# Hardware-Neuron.net
KiCad netlist of a schematic drawn in EAGLE
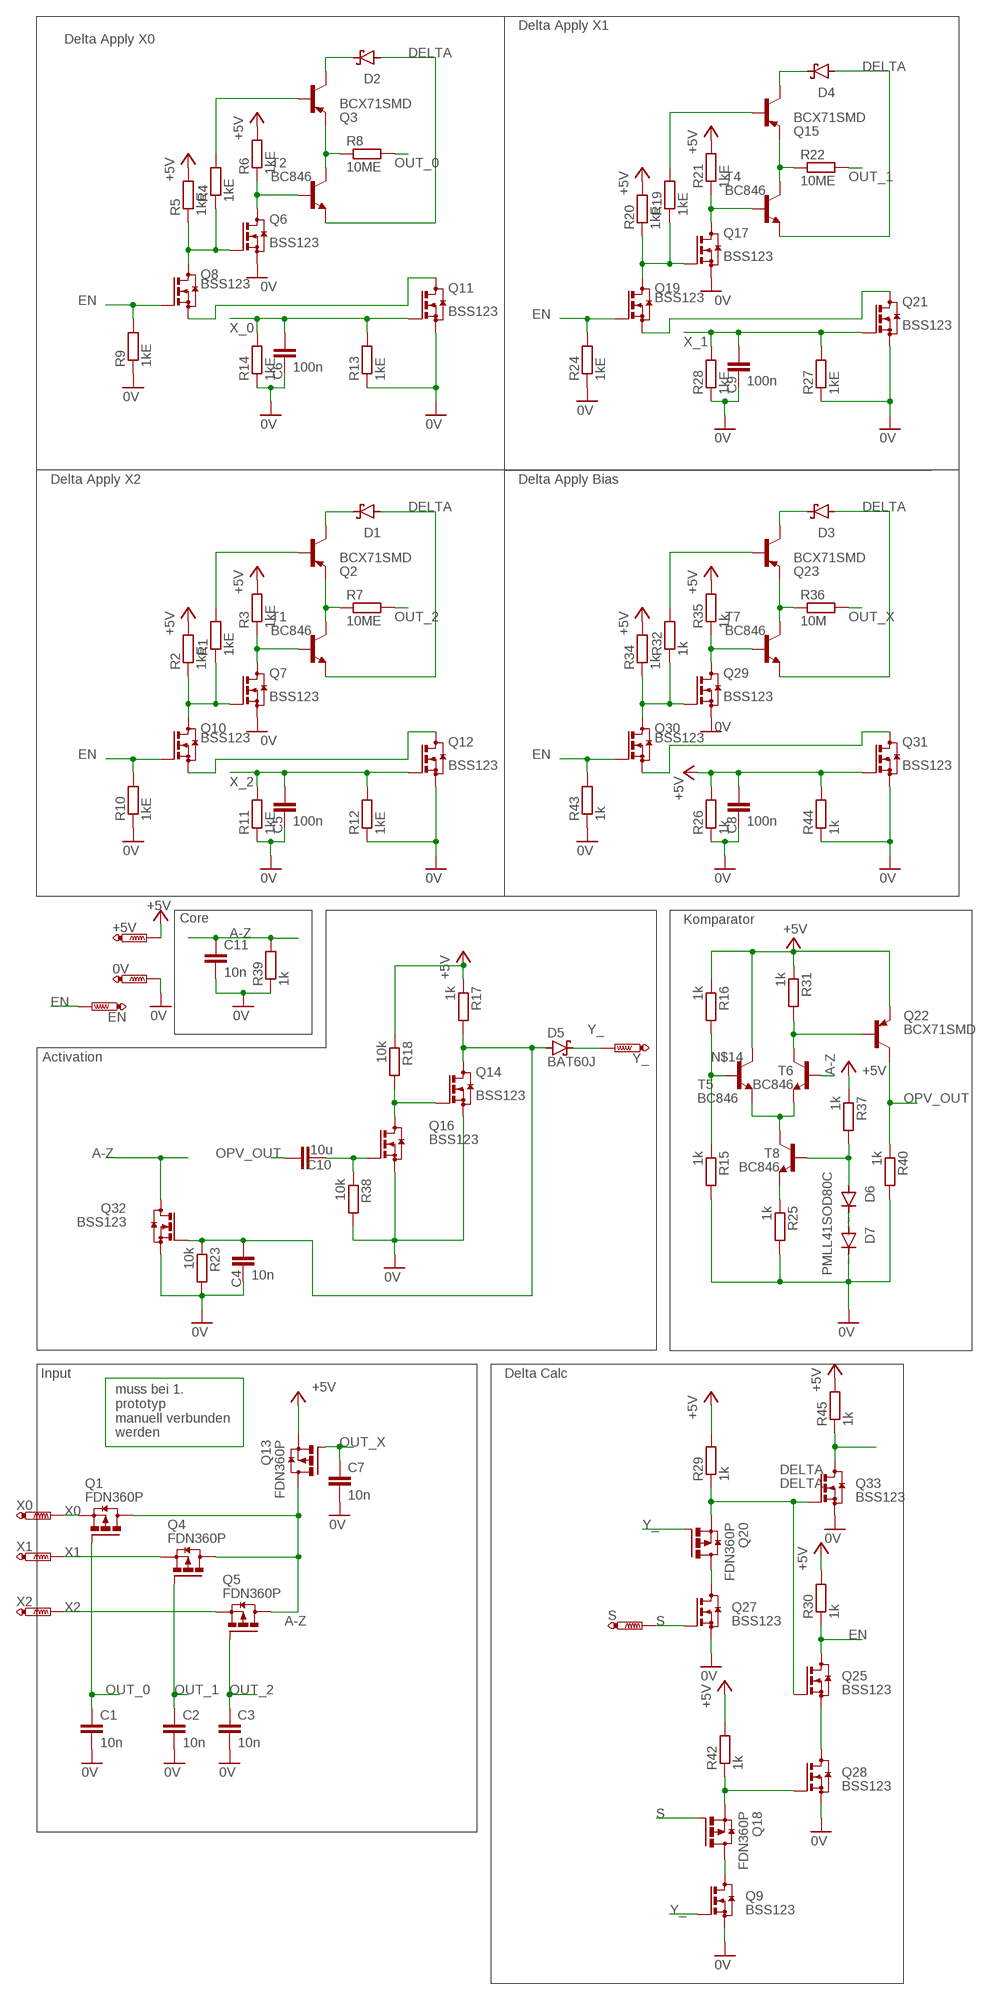
[diagram p0: schematic, sheet 1]

(export (version "E")
  (design (tool "Eeschema 10.0.6"))
  (components
    (comp (ref "+5V")
      (value "PTR1PAD1-17")
      (footprint "eagle-import:P1-17")
      (libsource (lib "eagle-import") (part "PTR1PAD1-17"))
    )
    (comp (ref "0V")
      (value "PTR1PAD1-17")
      (footprint "eagle-import:P1-17")
      (libsource (lib "eagle-import") (part "PTR1PAD1-17"))
    )
    (comp (ref "C1")
      (value "10n")
      (footprint "eagle-import:C0805")
      (libsource (lib "eagle-import") (part "C-EUC0805"))
    )
    (comp (ref "C2")
      (value "10n")
      (footprint "eagle-import:C0805")
      (libsource (lib "eagle-import") (part "C-EUC0805"))
    )
    (comp (ref "C3")
      (value "10n")
      (footprint "eagle-import:C0805")
      (libsource (lib "eagle-import") (part "C-EUC0805"))
    )
    (comp (ref "C4")
      (value "10n")
      (footprint "eagle-import:C0805")
      (libsource (lib "eagle-import") (part "C-EUC0805"))
    )
    (comp (ref "C5")
      (value "100n")
      (footprint "eagle-import:C0805")
      (libsource (lib "eagle-import") (part "C-EUC0805"))
    )
    (comp (ref "C6")
      (value "100n")
      (footprint "eagle-import:C0805")
      (libsource (lib "eagle-import") (part "C-EUC0805"))
    )
    (comp (ref "C7")
      (value "10n")
      (footprint "eagle-import:C0805")
      (libsource (lib "eagle-import") (part "C-EUC0805"))
    )
    (comp (ref "C8")
      (value "100n")
      (footprint "eagle-import:C0805")
      (libsource (lib "eagle-import") (part "C-EUC0805"))
    )
    (comp (ref "C9")
      (value "100n")
      (footprint "eagle-import:C0805")
      (libsource (lib "eagle-import") (part "C-EUC0805"))
    )
    (comp (ref "C10")
      (value "10u")
      (footprint "eagle-import:C0805")
      (libsource (lib "eagle-import") (part "C-EUC0805"))
    )
    (comp (ref "C11")
      (value "10n")
      (footprint "eagle-import:C0805")
      (libsource (lib "eagle-import") (part "C-EUC0805"))
    )
    (comp (ref "D1")
      (value "BAT60J")
      (footprint "eagle-import:SOD323_ST")
      (libsource (lib "eagle-import") (part "BAT60J"))
    )
    (comp (ref "D2")
      (value "BAT60J")
      (footprint "eagle-import:SOD323_ST")
      (libsource (lib "eagle-import") (part "BAT60J"))
    )
    (comp (ref "D3")
      (value "BAT60J")
      (footprint "eagle-import:SOD323_ST")
      (libsource (lib "eagle-import") (part "BAT60J"))
    )
    (comp (ref "D4")
      (value "BAT60J")
      (footprint "eagle-import:SOD323_ST")
      (libsource (lib "eagle-import") (part "BAT60J"))
    )
    (comp (ref "D5")
      (value "BAT60J")
      (footprint "eagle-import:SOD323_ST")
      (libsource (lib "eagle-import") (part "BAT60J"))
    )
    (comp (ref "D6")
      (value "PMLL41SOD80C")
      (footprint "eagle-import:SOD80C")
      (libsource (lib "eagle-import") (part "PMLL41SOD80C"))
    )
    (comp (ref "D7")
      (value "PMLL41SOD80C")
      (footprint "eagle-import:SOD80C")
      (libsource (lib "eagle-import") (part "PMLL41SOD80C"))
    )
    (comp (ref "EN")
      (value "PTR1PAD1-17")
      (footprint "eagle-import:P1-17")
      (libsource (lib "eagle-import") (part "PTR1PAD1-17"))
    )
    (comp (ref "Q1")
      (value "FDN360P")
      (footprint "eagle-import:SUPER-SOT3")
      (libsource (lib "eagle-import") (part "FDN360P"))
    )
    (comp (ref "Q2")
      (value "BCX71SMD")
      (footprint "eagle-import:SOT23")
      (libsource (lib "eagle-import") (part "BCX71SMD"))
    )
    (comp (ref "Q3")
      (value "BCX71SMD")
      (footprint "eagle-import:SOT23")
      (libsource (lib "eagle-import") (part "BCX71SMD"))
    )
    (comp (ref "Q4")
      (value "FDN360P")
      (footprint "eagle-import:SUPER-SOT3")
      (libsource (lib "eagle-import") (part "FDN360P"))
    )
    (comp (ref "Q5")
      (value "FDN360P")
      (footprint "eagle-import:SUPER-SOT3")
      (libsource (lib "eagle-import") (part "FDN360P"))
    )
    (comp (ref "Q6")
      (value "BSS123")
      (footprint "eagle-import:SOT23")
      (libsource (lib "eagle-import") (part "BSS123"))
    )
    (comp (ref "Q7")
      (value "BSS123")
      (footprint "eagle-import:SOT23")
      (libsource (lib "eagle-import") (part "BSS123"))
    )
    (comp (ref "Q8")
      (value "BSS123")
      (footprint "eagle-import:SOT23")
      (libsource (lib "eagle-import") (part "BSS123"))
    )
    (comp (ref "Q9")
      (value "BSS123")
      (footprint "eagle-import:SOT23")
      (libsource (lib "eagle-import") (part "BSS123"))
    )
    (comp (ref "Q10")
      (value "BSS123")
      (footprint "eagle-import:SOT23")
      (libsource (lib "eagle-import") (part "BSS123"))
    )
    (comp (ref "Q11")
      (value "BSS123")
      (footprint "eagle-import:SOT23")
      (libsource (lib "eagle-import") (part "BSS123"))
    )
    (comp (ref "Q12")
      (value "BSS123")
      (footprint "eagle-import:SOT23")
      (libsource (lib "eagle-import") (part "BSS123"))
    )
    (comp (ref "Q13")
      (value "FDN360P")
      (footprint "eagle-import:SUPER-SOT3")
      (libsource (lib "eagle-import") (part "FDN360P"))
    )
    (comp (ref "Q14")
      (value "BSS123")
      (footprint "eagle-import:SOT23")
      (libsource (lib "eagle-import") (part "BSS123"))
    )
    (comp (ref "Q15")
      (value "BCX71SMD")
      (footprint "eagle-import:SOT23")
      (libsource (lib "eagle-import") (part "BCX71SMD"))
    )
    (comp (ref "Q16")
      (value "BSS123")
      (footprint "eagle-import:SOT23")
      (libsource (lib "eagle-import") (part "BSS123"))
    )
    (comp (ref "Q17")
      (value "BSS123")
      (footprint "eagle-import:SOT23")
      (libsource (lib "eagle-import") (part "BSS123"))
    )
    (comp (ref "Q18")
      (value "FDN360P")
      (footprint "eagle-import:SUPER-SOT3")
      (libsource (lib "eagle-import") (part "FDN360P"))
    )
    (comp (ref "Q19")
      (value "BSS123")
      (footprint "eagle-import:SOT23")
      (libsource (lib "eagle-import") (part "BSS123"))
    )
    (comp (ref "Q20")
      (value "FDN360P")
      (footprint "eagle-import:SUPER-SOT3")
      (libsource (lib "eagle-import") (part "FDN360P"))
    )
    (comp (ref "Q21")
      (value "BSS123")
      (footprint "eagle-import:SOT23")
      (libsource (lib "eagle-import") (part "BSS123"))
    )
    (comp (ref "Q22")
      (value "BCX71SMD")
      (footprint "eagle-import:SOT23")
      (libsource (lib "eagle-import") (part "BCX71SMD"))
    )
    (comp (ref "Q23")
      (value "BCX71SMD")
      (footprint "eagle-import:SOT23")
      (libsource (lib "eagle-import") (part "BCX71SMD"))
    )
    (comp (ref "Q25")
      (value "BSS123")
      (footprint "eagle-import:SOT23")
      (libsource (lib "eagle-import") (part "BSS123"))
    )
    (comp (ref "Q27")
      (value "BSS123")
      (footprint "eagle-import:SOT23")
      (libsource (lib "eagle-import") (part "BSS123"))
    )
    (comp (ref "Q28")
      (value "BSS123")
      (footprint "eagle-import:SOT23")
      (libsource (lib "eagle-import") (part "BSS123"))
    )
    (comp (ref "Q29")
      (value "BSS123")
      (footprint "eagle-import:SOT23")
      (libsource (lib "eagle-import") (part "BSS123"))
    )
    (comp (ref "Q30")
      (value "BSS123")
      (footprint "eagle-import:SOT23")
      (libsource (lib "eagle-import") (part "BSS123"))
    )
    (comp (ref "Q31")
      (value "BSS123")
      (footprint "eagle-import:SOT23")
      (libsource (lib "eagle-import") (part "BSS123"))
    )
    (comp (ref "Q32")
      (value "BSS123")
      (footprint "eagle-import:SOT23")
      (libsource (lib "eagle-import") (part "BSS123"))
    )
    (comp (ref "Q33")
      (value "BSS123")
      (footprint "eagle-import:SOT23")
      (libsource (lib "eagle-import") (part "BSS123"))
    )
    (comp (ref "R1")
      (value "1kE")
      (footprint "eagle-import:M0805")
      (libsource (lib "eagle-import") (part "R-EU_M0805"))
    )
    (comp (ref "R2")
      (value "1kE")
      (footprint "eagle-import:M0805")
      (libsource (lib "eagle-import") (part "R-EU_M0805"))
    )
    (comp (ref "R3")
      (value "1kE")
      (footprint "eagle-import:M0805")
      (libsource (lib "eagle-import") (part "R-EU_M0805"))
    )
    (comp (ref "R4")
      (value "1kE")
      (footprint "eagle-import:M0805")
      (libsource (lib "eagle-import") (part "R-EU_M0805"))
    )
    (comp (ref "R5")
      (value "1kE")
      (footprint "eagle-import:M0805")
      (libsource (lib "eagle-import") (part "R-EU_M0805"))
    )
    (comp (ref "R6")
      (value "1kE")
      (footprint "eagle-import:M0805")
      (libsource (lib "eagle-import") (part "R-EU_M0805"))
    )
    (comp (ref "R7")
      (value "10ME")
      (footprint "eagle-import:M0805")
      (libsource (lib "eagle-import") (part "R-EU_M0805"))
    )
    (comp (ref "R8")
      (value "10ME")
      (footprint "eagle-import:M0805")
      (libsource (lib "eagle-import") (part "R-EU_M0805"))
    )
    (comp (ref "R9")
      (value "1kE")
      (footprint "eagle-import:M0805")
      (libsource (lib "eagle-import") (part "R-EU_M0805"))
    )
    (comp (ref "R10")
      (value "1kE")
      (footprint "eagle-import:M0805")
      (libsource (lib "eagle-import") (part "R-EU_M0805"))
    )
    (comp (ref "R11")
      (value "1kE")
      (footprint "eagle-import:M0805")
      (libsource (lib "eagle-import") (part "R-EU_M0805"))
    )
    (comp (ref "R12")
      (value "1kE")
      (footprint "eagle-import:M0805")
      (libsource (lib "eagle-import") (part "R-EU_M0805"))
    )
    (comp (ref "R13")
      (value "1kE")
      (footprint "eagle-import:M0805")
      (libsource (lib "eagle-import") (part "R-EU_M0805"))
    )
    (comp (ref "R14")
      (value "1kE")
      (footprint "eagle-import:M0805")
      (libsource (lib "eagle-import") (part "R-EU_M0805"))
    )
    (comp (ref "R15")
      (value "1k")
      (footprint "eagle-import:M0805")
      (libsource (lib "eagle-import") (part "R-EU_M0805"))
    )
    (comp (ref "R16")
      (value "1k")
      (footprint "eagle-import:M0805")
      (libsource (lib "eagle-import") (part "R-EU_M0805"))
    )
    (comp (ref "R17")
      (value "1k")
      (footprint "eagle-import:M0805")
      (libsource (lib "eagle-import") (part "R-EU_M0805"))
    )
    (comp (ref "R18")
      (value "10k")
      (footprint "eagle-import:M0805")
      (libsource (lib "eagle-import") (part "R-EU_M0805"))
    )
    (comp (ref "R19")
      (value "1kE")
      (footprint "eagle-import:M0805")
      (libsource (lib "eagle-import") (part "R-EU_M0805"))
    )
    (comp (ref "R20")
      (value "1kE")
      (footprint "eagle-import:M0805")
      (libsource (lib "eagle-import") (part "R-EU_M0805"))
    )
    (comp (ref "R21")
      (value "1kE")
      (footprint "eagle-import:M0805")
      (libsource (lib "eagle-import") (part "R-EU_M0805"))
    )
    (comp (ref "R22")
      (value "10ME")
      (footprint "eagle-import:M0805")
      (libsource (lib "eagle-import") (part "R-EU_M0805"))
    )
    (comp (ref "R23")
      (value "10k")
      (footprint "eagle-import:M0805")
      (libsource (lib "eagle-import") (part "R-EU_M0805"))
    )
    (comp (ref "R24")
      (value "1kE")
      (footprint "eagle-import:M0805")
      (libsource (lib "eagle-import") (part "R-EU_M0805"))
    )
    (comp (ref "R25")
      (value "1k")
      (footprint "eagle-import:M0805")
      (libsource (lib "eagle-import") (part "R-EU_M0805"))
    )
    (comp (ref "R26")
      (value "1k")
      (footprint "eagle-import:M0805")
      (libsource (lib "eagle-import") (part "R-EU_M0805"))
    )
    (comp (ref "R27")
      (value "1kE")
      (footprint "eagle-import:M0805")
      (libsource (lib "eagle-import") (part "R-EU_M0805"))
    )
    (comp (ref "R28")
      (value "1kE")
      (footprint "eagle-import:M0805")
      (libsource (lib "eagle-import") (part "R-EU_M0805"))
    )
    (comp (ref "R29")
      (value "1k")
      (footprint "eagle-import:M0805")
      (libsource (lib "eagle-import") (part "R-EU_M0805"))
    )
    (comp (ref "R30")
      (value "1k")
      (footprint "eagle-import:M0805")
      (libsource (lib "eagle-import") (part "R-EU_M0805"))
    )
    (comp (ref "R31")
      (value "1k")
      (footprint "eagle-import:M0805")
      (libsource (lib "eagle-import") (part "R-EU_M0805"))
    )
    (comp (ref "R32")
      (value "1k")
      (footprint "eagle-import:M0805")
      (libsource (lib "eagle-import") (part "R-EU_M0805"))
    )
    (comp (ref "R34")
      (value "1k")
      (footprint "eagle-import:M0805")
      (libsource (lib "eagle-import") (part "R-EU_M0805"))
    )
    (comp (ref "R35")
      (value "1k")
      (footprint "eagle-import:M0805")
      (libsource (lib "eagle-import") (part "R-EU_M0805"))
    )
    (comp (ref "R36")
      (value "10M")
      (footprint "eagle-import:M0805")
      (libsource (lib "eagle-import") (part "R-EU_M0805"))
    )
    (comp (ref "R37")
      (value "1k")
      (footprint "eagle-import:M0805")
      (libsource (lib "eagle-import") (part "R-EU_M0805"))
    )
    (comp (ref "R38")
      (value "10k")
      (footprint "eagle-import:M0805")
      (libsource (lib "eagle-import") (part "R-EU_M0805"))
    )
    (comp (ref "R39")
      (value "1k")
      (footprint "eagle-import:M0805")
      (libsource (lib "eagle-import") (part "R-EU_M0805"))
    )
    (comp (ref "R40")
      (value "1k")
      (footprint "eagle-import:M0805")
      (libsource (lib "eagle-import") (part "R-EU_M0805"))
    )
    (comp (ref "R42")
      (value "1k")
      (footprint "eagle-import:M0805")
      (libsource (lib "eagle-import") (part "R-EU_M0805"))
    )
    (comp (ref "R43")
      (value "1k")
      (footprint "eagle-import:M0805")
      (libsource (lib "eagle-import") (part "R-EU_M0805"))
    )
    (comp (ref "R44")
      (value "1k")
      (footprint "eagle-import:M0805")
      (libsource (lib "eagle-import") (part "R-EU_M0805"))
    )
    (comp (ref "R45")
      (value "1k")
      (footprint "eagle-import:M0805")
      (libsource (lib "eagle-import") (part "R-EU_M0805"))
    )
    (comp (ref "S")
      (value "PTR1PAD1-17")
      (footprint "eagle-import:P1-17")
      (libsource (lib "eagle-import") (part "PTR1PAD1-17"))
    )
    (comp (ref "T1")
      (value "BC846")
      (footprint "eagle-import:SOT23")
      (libsource (lib "eagle-import") (part "BC846"))
    )
    (comp (ref "T2")
      (value "BC846")
      (footprint "eagle-import:SOT23")
      (libsource (lib "eagle-import") (part "BC846"))
    )
    (comp (ref "T4")
      (value "BC846")
      (footprint "eagle-import:SOT23")
      (libsource (lib "eagle-import") (part "BC846"))
    )
    (comp (ref "T5")
      (value "BC846")
      (footprint "eagle-import:SOT23")
      (libsource (lib "eagle-import") (part "BC846"))
    )
    (comp (ref "T6")
      (value "BC846")
      (footprint "eagle-import:SOT23")
      (libsource (lib "eagle-import") (part "BC846"))
    )
    (comp (ref "T7")
      (value "BC846")
      (footprint "eagle-import:SOT23")
      (libsource (lib "eagle-import") (part "BC846"))
    )
    (comp (ref "T8")
      (value "BC846")
      (footprint "eagle-import:SOT23")
      (libsource (lib "eagle-import") (part "BC846"))
    )
    (comp (ref "X0")
      (value "PTR1PAD1-17")
      (footprint "eagle-import:P1-17")
      (libsource (lib "eagle-import") (part "PTR1PAD1-17"))
    )
    (comp (ref "X1")
      (value "PTR1PAD1-17")
      (footprint "eagle-import:P1-17")
      (libsource (lib "eagle-import") (part "PTR1PAD1-17"))
    )
    (comp (ref "X2")
      (value "PTR1PAD1-17")
      (footprint "eagle-import:P1-17")
      (libsource (lib "eagle-import") (part "PTR1PAD1-17"))
    )
    (comp (ref "Y_")
      (value "PTR1PAD1-17")
      (footprint "eagle-import:P1-17")
      (libsource (lib "eagle-import") (part "PTR1PAD1-17"))
    )
  )
  (nets
    (net (code "1") (name "+5V") (class "Default")
      (node (ref "+5V") (pin "TP") (pinfunction "TP_TP") (pintype "input"))
      (node (ref "C8") (pin "1") (pinfunction "1_1") (pintype "passive"))
      (node (ref "Q13") (pin "2") (pinfunction "S_2") (pintype "passive"))
      (node (ref "Q22") (pin "2") (pinfunction "E_2") (pintype "passive"))
      (node (ref "Q31") (pin "1") (pinfunction "G_1") (pintype "passive"))
      (node (ref "R16") (pin "1") (pinfunction "1_1") (pintype "passive"))
      (node (ref "R17") (pin "1") (pinfunction "1_1") (pintype "passive"))
      (node (ref "R18") (pin "1") (pinfunction "1_1") (pintype "passive"))
      (node (ref "R2") (pin "2") (pinfunction "2_2") (pintype "passive"))
      (node (ref "R20") (pin "2") (pinfunction "2_2") (pintype "passive"))
      (node (ref "R21") (pin "2") (pinfunction "2_2") (pintype "passive"))
      (node (ref "R26") (pin "2") (pinfunction "2_2") (pintype "passive"))
      (node (ref "R29") (pin "2") (pinfunction "2_2") (pintype "passive"))
      (node (ref "R3") (pin "2") (pinfunction "2_2") (pintype "passive"))
      (node (ref "R30") (pin "2") (pinfunction "2_2") (pintype "passive"))
      (node (ref "R31") (pin "1") (pinfunction "1_1") (pintype "passive"))
      (node (ref "R34") (pin "2") (pinfunction "2_2") (pintype "passive"))
      (node (ref "R35") (pin "2") (pinfunction "2_2") (pintype "passive"))
      (node (ref "R37") (pin "1") (pinfunction "1_1") (pintype "passive"))
      (node (ref "R42") (pin "2") (pinfunction "2_2") (pintype "passive"))
      (node (ref "R44") (pin "2") (pinfunction "2_2") (pintype "passive"))
      (node (ref "R45") (pin "2") (pinfunction "2_2") (pintype "passive"))
      (node (ref "R5") (pin "2") (pinfunction "2_2") (pintype "passive"))
      (node (ref "R6") (pin "2") (pinfunction "2_2") (pintype "passive"))
      (node (ref "T5") (pin "3") (pinfunction "C_3") (pintype "passive"))
    )
    (net (code "2") (name "/A-Z") (class "Default")
      (node (ref "C11") (pin "1") (pinfunction "1_1") (pintype "passive"))
      (node (ref "Q1") (pin "3") (pinfunction "D_3") (pintype "passive"))
      (node (ref "Q13") (pin "3") (pinfunction "D_3") (pintype "passive"))
      (node (ref "Q32") (pin "3") (pinfunction "D_3") (pintype "passive"))
      (node (ref "Q4") (pin "3") (pinfunction "D_3") (pintype "passive"))
      (node (ref "Q5") (pin "3") (pinfunction "D_3") (pintype "passive"))
      (node (ref "R39") (pin "2") (pinfunction "2_2") (pintype "passive"))
      (node (ref "T6") (pin "1") (pinfunction "B_1") (pintype "passive"))
    )
    (net (code "3") (name "/DELTA") (class "Default")
      (node (ref "D1") (pin "A") (pinfunction "A_A") (pintype "passive"))
      (node (ref "D2") (pin "A") (pinfunction "A_A") (pintype "passive"))
      (node (ref "D3") (pin "A") (pinfunction "A_A") (pintype "passive"))
      (node (ref "D4") (pin "A") (pinfunction "A_A") (pintype "passive"))
      (node (ref "Q20") (pin "2") (pinfunction "S_2") (pintype "passive"))
      (node (ref "Q25") (pin "1") (pinfunction "G_1") (pintype "passive"))
      (node (ref "Q33") (pin "1") (pinfunction "G_1") (pintype "passive"))
      (node (ref "R29") (pin "1") (pinfunction "1_1") (pintype "passive"))
      (node (ref "T1") (pin "2") (pinfunction "E_2") (pintype "passive"))
      (node (ref "T2") (pin "2") (pinfunction "E_2") (pintype "passive"))
      (node (ref "T4") (pin "2") (pinfunction "E_2") (pintype "passive"))
      (node (ref "T7") (pin "2") (pinfunction "E_2") (pintype "passive"))
    )
    (net (code "4") (name "/EN") (class "Default")
      (node (ref "EN") (pin "TP") (pinfunction "TP_TP") (pintype "input"))
      (node (ref "Q10") (pin "1") (pinfunction "G_1") (pintype "passive"))
      (node (ref "Q19") (pin "1") (pinfunction "G_1") (pintype "passive"))
      (node (ref "Q25") (pin "3") (pinfunction "D_3") (pintype "passive"))
      (node (ref "Q30") (pin "1") (pinfunction "G_1") (pintype "passive"))
      (node (ref "Q8") (pin "1") (pinfunction "G_1") (pintype "passive"))
      (node (ref "R10") (pin "2") (pinfunction "2_2") (pintype "passive"))
      (node (ref "R24") (pin "2") (pinfunction "2_2") (pintype "passive"))
      (node (ref "R30") (pin "1") (pinfunction "1_1") (pintype "passive"))
      (node (ref "R43") (pin "2") (pinfunction "2_2") (pintype "passive"))
      (node (ref "R9") (pin "2") (pinfunction "2_2") (pintype "passive"))
    )
    (net (code "5") (name "/N$14") (class "Default")
      (node (ref "R15") (pin "1") (pinfunction "1_1") (pintype "passive"))
      (node (ref "R16") (pin "2") (pinfunction "2_2") (pintype "passive"))
      (node (ref "T5") (pin "1") (pinfunction "B_1") (pintype "passive"))
    )
    (net (code "6") (name "/OPV_OUT") (class "Default")
      (node (ref "C10") (pin "1") (pinfunction "1_1") (pintype "passive"))
      (node (ref "Q22") (pin "3") (pinfunction "C_3") (pintype "passive"))
      (node (ref "R40") (pin "1") (pinfunction "1_1") (pintype "passive"))
    )
    (net (code "7") (name "/OUT_0") (class "Default")
      (node (ref "C1") (pin "1") (pinfunction "1_1") (pintype "passive"))
      (node (ref "Q1") (pin "1") (pinfunction "G_1") (pintype "passive"))
      (node (ref "R8") (pin "2") (pinfunction "2_2") (pintype "passive"))
    )
    (net (code "8") (name "/OUT_1") (class "Default")
      (node (ref "C2") (pin "1") (pinfunction "1_1") (pintype "passive"))
      (node (ref "Q4") (pin "1") (pinfunction "G_1") (pintype "passive"))
      (node (ref "R22") (pin "2") (pinfunction "2_2") (pintype "passive"))
    )
    (net (code "9") (name "/OUT_2") (class "Default")
      (node (ref "C3") (pin "1") (pinfunction "1_1") (pintype "passive"))
      (node (ref "Q5") (pin "1") (pinfunction "G_1") (pintype "passive"))
      (node (ref "R7") (pin "2") (pinfunction "2_2") (pintype "passive"))
    )
    (net (code "10") (name "/OUT_X") (class "Default")
      (node (ref "C7") (pin "1") (pinfunction "1_1") (pintype "passive"))
      (node (ref "Q13") (pin "1") (pinfunction "G_1") (pintype "passive"))
      (node (ref "R36") (pin "2") (pinfunction "2_2") (pintype "passive"))
    )
    (net (code "11") (name "/S") (class "Default")
      (node (ref "Q18") (pin "1") (pinfunction "G_1") (pintype "passive"))
      (node (ref "Q27") (pin "1") (pinfunction "G_1") (pintype "passive"))
      (node (ref "S") (pin "TP") (pinfunction "TP_TP") (pintype "input"))
    )
    (net (code "12") (name "/X0") (class "Default")
      (node (ref "Q1") (pin "2") (pinfunction "S_2") (pintype "passive"))
      (node (ref "X0") (pin "TP") (pinfunction "TP_TP") (pintype "input"))
    )
    (net (code "13") (name "/X1") (class "Default")
      (node (ref "Q4") (pin "2") (pinfunction "S_2") (pintype "passive"))
      (node (ref "X1") (pin "TP") (pinfunction "TP_TP") (pintype "input"))
    )
    (net (code "14") (name "/X2") (class "Default")
      (node (ref "Q5") (pin "2") (pinfunction "S_2") (pintype "passive"))
      (node (ref "X2") (pin "TP") (pinfunction "TP_TP") (pintype "input"))
    )
    (net (code "15") (name "/X_0") (class "Default")
      (node (ref "C6") (pin "1") (pinfunction "1_1") (pintype "passive"))
      (node (ref "Q11") (pin "1") (pinfunction "G_1") (pintype "passive"))
      (node (ref "R13") (pin "2") (pinfunction "2_2") (pintype "passive"))
      (node (ref "R14") (pin "2") (pinfunction "2_2") (pintype "passive"))
    )
    (net (code "16") (name "/X_1") (class "Default")
      (node (ref "C9") (pin "1") (pinfunction "1_1") (pintype "passive"))
      (node (ref "Q21") (pin "1") (pinfunction "G_1") (pintype "passive"))
      (node (ref "R27") (pin "2") (pinfunction "2_2") (pintype "passive"))
      (node (ref "R28") (pin "2") (pinfunction "2_2") (pintype "passive"))
    )
    (net (code "17") (name "/X_2") (class "Default")
      (node (ref "C5") (pin "1") (pinfunction "1_1") (pintype "passive"))
      (node (ref "Q12") (pin "1") (pinfunction "G_1") (pintype "passive"))
      (node (ref "R11") (pin "2") (pinfunction "2_2") (pintype "passive"))
      (node (ref "R12") (pin "2") (pinfunction "2_2") (pintype "passive"))
    )
    (net (code "18") (name "/Y_") (class "Default")
      (node (ref "D5") (pin "C") (pinfunction "C_C") (pintype "passive"))
      (node (ref "Q20") (pin "1") (pinfunction "G_1") (pintype "passive"))
      (node (ref "Q9") (pin "1") (pinfunction "G_1") (pintype "passive"))
      (node (ref "Y_") (pin "TP") (pinfunction "TP_TP") (pintype "input"))
    )
    (net (code "19") (name "0V") (class "Default")
      (node (ref "0V") (pin "TP") (pinfunction "TP_TP") (pintype "input"))
      (node (ref "C1") (pin "2") (pinfunction "2_2") (pintype "passive"))
      (node (ref "C11") (pin "2") (pinfunction "2_2") (pintype "passive"))
      (node (ref "C2") (pin "2") (pinfunction "2_2") (pintype "passive"))
      (node (ref "C3") (pin "2") (pinfunction "2_2") (pintype "passive"))
      (node (ref "C4") (pin "2") (pinfunction "2_2") (pintype "passive"))
      (node (ref "C5") (pin "2") (pinfunction "2_2") (pintype "passive"))
      (node (ref "C6") (pin "2") (pinfunction "2_2") (pintype "passive"))
      (node (ref "C7") (pin "2") (pinfunction "2_2") (pintype "passive"))
      (node (ref "C8") (pin "2") (pinfunction "2_2") (pintype "passive"))
      (node (ref "C9") (pin "2") (pinfunction "2_2") (pintype "passive"))
      (node (ref "D7") (pin "C") (pinfunction "C_C") (pintype "passive"))
      (node (ref "Q11") (pin "2") (pinfunction "S_2") (pintype "passive"))
      (node (ref "Q12") (pin "2") (pinfunction "S_2") (pintype "passive"))
      (node (ref "Q14") (pin "2") (pinfunction "S_2") (pintype "passive"))
      (node (ref "Q16") (pin "2") (pinfunction "S_2") (pintype "passive"))
      (node (ref "Q17") (pin "2") (pinfunction "S_2") (pintype "passive"))
      (node (ref "Q21") (pin "2") (pinfunction "S_2") (pintype "passive"))
      (node (ref "Q27") (pin "2") (pinfunction "S_2") (pintype "passive"))
      (node (ref "Q28") (pin "2") (pinfunction "S_2") (pintype "passive"))
      (node (ref "Q29") (pin "2") (pinfunction "S_2") (pintype "passive"))
      (node (ref "Q31") (pin "2") (pinfunction "S_2") (pintype "passive"))
      (node (ref "Q32") (pin "2") (pinfunction "S_2") (pintype "passive"))
      (node (ref "Q33") (pin "2") (pinfunction "S_2") (pintype "passive"))
      (node (ref "Q6") (pin "2") (pinfunction "S_2") (pintype "passive"))
      (node (ref "Q7") (pin "2") (pinfunction "S_2") (pintype "passive"))
      (node (ref "Q9") (pin "2") (pinfunction "S_2") (pintype "passive"))
      (node (ref "R10") (pin "1") (pinfunction "1_1") (pintype "passive"))
      (node (ref "R11") (pin "1") (pinfunction "1_1") (pintype "passive"))
      (node (ref "R12") (pin "1") (pinfunction "1_1") (pintype "passive"))
      (node (ref "R13") (pin "1") (pinfunction "1_1") (pintype "passive"))
      (node (ref "R14") (pin "1") (pinfunction "1_1") (pintype "passive"))
      (node (ref "R15") (pin "2") (pinfunction "2_2") (pintype "passive"))
      (node (ref "R23") (pin "2") (pinfunction "2_2") (pintype "passive"))
      (node (ref "R24") (pin "1") (pinfunction "1_1") (pintype "passive"))
      (node (ref "R25") (pin "2") (pinfunction "2_2") (pintype "passive"))
      (node (ref "R26") (pin "1") (pinfunction "1_1") (pintype "passive"))
      (node (ref "R27") (pin "1") (pinfunction "1_1") (pintype "passive"))
      (node (ref "R28") (pin "1") (pinfunction "1_1") (pintype "passive"))
      (node (ref "R38") (pin "2") (pinfunction "2_2") (pintype "passive"))
      (node (ref "R39") (pin "1") (pinfunction "1_1") (pintype "passive"))
      (node (ref "R40") (pin "2") (pinfunction "2_2") (pintype "passive"))
      (node (ref "R43") (pin "1") (pinfunction "1_1") (pintype "passive"))
      (node (ref "R44") (pin "1") (pinfunction "1_1") (pintype "passive"))
      (node (ref "R9") (pin "1") (pinfunction "1_1") (pintype "passive"))
    )
    (net (code "20") (name "Net-(D6-PadC)") (class "Default")
      (node (ref "D6") (pin "C") (pinfunction "C_C") (pintype "passive"))
      (node (ref "D7") (pin "A") (pinfunction "A_A") (pintype "passive"))
    )
    (net (code "21") (name "Net-(Q2-B)") (class "Default")
      (node (ref "Q2") (pin "1") (pinfunction "B_1") (pintype "passive"))
      (node (ref "R1") (pin "2") (pinfunction "2_2") (pintype "passive"))
    )
    (net (code "22") (name "Net-(Q2-C)") (class "Default")
      (node (ref "D1") (pin "C") (pinfunction "C_C") (pintype "passive"))
      (node (ref "Q2") (pin "3") (pinfunction "C_3") (pintype "passive"))
    )
    (net (code "23") (name "Net-(Q2-E)") (class "Default")
      (node (ref "Q2") (pin "2") (pinfunction "E_2") (pintype "passive"))
      (node (ref "R7") (pin "1") (pinfunction "1_1") (pintype "passive"))
      (node (ref "T1") (pin "3") (pinfunction "C_3") (pintype "passive"))
    )
    (net (code "24") (name "Net-(Q3-B)") (class "Default")
      (node (ref "Q3") (pin "1") (pinfunction "B_1") (pintype "passive"))
      (node (ref "R4") (pin "2") (pinfunction "2_2") (pintype "passive"))
    )
    (net (code "25") (name "Net-(Q3-C)") (class "Default")
      (node (ref "D2") (pin "C") (pinfunction "C_C") (pintype "passive"))
      (node (ref "Q3") (pin "3") (pinfunction "C_3") (pintype "passive"))
    )
    (net (code "26") (name "Net-(Q3-E)") (class "Default")
      (node (ref "Q3") (pin "2") (pinfunction "E_2") (pintype "passive"))
      (node (ref "R8") (pin "1") (pinfunction "1_1") (pintype "passive"))
      (node (ref "T2") (pin "3") (pinfunction "C_3") (pintype "passive"))
    )
    (net (code "27") (name "Net-(Q6-D)") (class "Default")
      (node (ref "Q6") (pin "3") (pinfunction "D_3") (pintype "passive"))
      (node (ref "R6") (pin "1") (pinfunction "1_1") (pintype "passive"))
      (node (ref "T2") (pin "1") (pinfunction "B_1") (pintype "passive"))
    )
    (net (code "28") (name "Net-(Q6-G)") (class "Default")
      (node (ref "Q6") (pin "1") (pinfunction "G_1") (pintype "passive"))
      (node (ref "Q8") (pin "3") (pinfunction "D_3") (pintype "passive"))
      (node (ref "R4") (pin "1") (pinfunction "1_1") (pintype "passive"))
      (node (ref "R5") (pin "1") (pinfunction "1_1") (pintype "passive"))
    )
    (net (code "29") (name "Net-(Q7-D)") (class "Default")
      (node (ref "Q7") (pin "3") (pinfunction "D_3") (pintype "passive"))
      (node (ref "R3") (pin "1") (pinfunction "1_1") (pintype "passive"))
      (node (ref "T1") (pin "1") (pinfunction "B_1") (pintype "passive"))
    )
    (net (code "30") (name "Net-(Q10-D)") (class "Default")
      (node (ref "Q10") (pin "3") (pinfunction "D_3") (pintype "passive"))
      (node (ref "Q7") (pin "1") (pinfunction "G_1") (pintype "passive"))
      (node (ref "R1") (pin "1") (pinfunction "1_1") (pintype "passive"))
      (node (ref "R2") (pin "1") (pinfunction "1_1") (pintype "passive"))
    )
    (net (code "31") (name "Net-(Q10-S)") (class "Default")
      (node (ref "Q10") (pin "2") (pinfunction "S_2") (pintype "passive"))
      (node (ref "Q12") (pin "3") (pinfunction "D_3") (pintype "passive"))
    )
    (net (code "32") (name "Net-(Q11-D)") (class "Default")
      (node (ref "Q11") (pin "3") (pinfunction "D_3") (pintype "passive"))
      (node (ref "Q8") (pin "2") (pinfunction "S_2") (pintype "passive"))
    )
    (net (code "33") (name "Net-(Q14-D)") (class "Default")
      (node (ref "C4") (pin "1") (pinfunction "1_1") (pintype "passive"))
      (node (ref "D5") (pin "A") (pinfunction "A_A") (pintype "passive"))
      (node (ref "Q14") (pin "3") (pinfunction "D_3") (pintype "passive"))
      (node (ref "Q32") (pin "1") (pinfunction "G_1") (pintype "passive"))
      (node (ref "R17") (pin "2") (pinfunction "2_2") (pintype "passive"))
      (node (ref "R23") (pin "1") (pinfunction "1_1") (pintype "passive"))
    )
    (net (code "34") (name "Net-(Q14-G)") (class "Default")
      (node (ref "Q14") (pin "1") (pinfunction "G_1") (pintype "passive"))
      (node (ref "Q16") (pin "3") (pinfunction "D_3") (pintype "passive"))
      (node (ref "R18") (pin "2") (pinfunction "2_2") (pintype "passive"))
    )
    (net (code "35") (name "Net-(Q15-B)") (class "Default")
      (node (ref "Q15") (pin "1") (pinfunction "B_1") (pintype "passive"))
      (node (ref "R19") (pin "2") (pinfunction "2_2") (pintype "passive"))
    )
    (net (code "36") (name "Net-(Q15-C)") (class "Default")
      (node (ref "D4") (pin "C") (pinfunction "C_C") (pintype "passive"))
      (node (ref "Q15") (pin "3") (pinfunction "C_3") (pintype "passive"))
    )
    (net (code "37") (name "Net-(Q15-E)") (class "Default")
      (node (ref "Q15") (pin "2") (pinfunction "E_2") (pintype "passive"))
      (node (ref "R22") (pin "1") (pinfunction "1_1") (pintype "passive"))
      (node (ref "T4") (pin "3") (pinfunction "C_3") (pintype "passive"))
    )
    (net (code "38") (name "Net-(Q16-G)") (class "Default")
      (node (ref "C10") (pin "2") (pinfunction "2_2") (pintype "passive"))
      (node (ref "Q16") (pin "1") (pinfunction "G_1") (pintype "passive"))
      (node (ref "R38") (pin "1") (pinfunction "1_1") (pintype "passive"))
    )
    (net (code "39") (name "Net-(Q17-D)") (class "Default")
      (node (ref "Q17") (pin "3") (pinfunction "D_3") (pintype "passive"))
      (node (ref "R21") (pin "1") (pinfunction "1_1") (pintype "passive"))
      (node (ref "T4") (pin "1") (pinfunction "B_1") (pintype "passive"))
    )
    (net (code "40") (name "Net-(Q17-G)") (class "Default")
      (node (ref "Q17") (pin "1") (pinfunction "G_1") (pintype "passive"))
      (node (ref "Q19") (pin "3") (pinfunction "D_3") (pintype "passive"))
      (node (ref "R19") (pin "1") (pinfunction "1_1") (pintype "passive"))
      (node (ref "R20") (pin "1") (pinfunction "1_1") (pintype "passive"))
    )
    (net (code "41") (name "Net-(Q18-D)") (class "Default")
      (node (ref "Q18") (pin "3") (pinfunction "D_3") (pintype "passive"))
      (node (ref "Q9") (pin "3") (pinfunction "D_3") (pintype "passive"))
    )
    (net (code "42") (name "Net-(Q18-S)") (class "Default")
      (node (ref "Q18") (pin "2") (pinfunction "S_2") (pintype "passive"))
      (node (ref "Q28") (pin "1") (pinfunction "G_1") (pintype "passive"))
      (node (ref "R42") (pin "1") (pinfunction "1_1") (pintype "passive"))
    )
    (net (code "43") (name "Net-(Q19-S)") (class "Default")
      (node (ref "Q19") (pin "2") (pinfunction "S_2") (pintype "passive"))
      (node (ref "Q21") (pin "3") (pinfunction "D_3") (pintype "passive"))
    )
    (net (code "44") (name "Net-(Q20-D)") (class "Default")
      (node (ref "Q20") (pin "3") (pinfunction "D_3") (pintype "passive"))
      (node (ref "Q27") (pin "3") (pinfunction "D_3") (pintype "passive"))
    )
    (net (code "45") (name "Net-(Q22-B)") (class "Default")
      (node (ref "Q22") (pin "1") (pinfunction "B_1") (pintype "passive"))
      (node (ref "R31") (pin "2") (pinfunction "2_2") (pintype "passive"))
      (node (ref "T6") (pin "3") (pinfunction "C_3") (pintype "passive"))
    )
    (net (code "46") (name "Net-(Q23-B)") (class "Default")
      (node (ref "Q23") (pin "1") (pinfunction "B_1") (pintype "passive"))
      (node (ref "R32") (pin "2") (pinfunction "2_2") (pintype "passive"))
    )
    (net (code "47") (name "Net-(Q23-C)") (class "Default")
      (node (ref "D3") (pin "C") (pinfunction "C_C") (pintype "passive"))
      (node (ref "Q23") (pin "3") (pinfunction "C_3") (pintype "passive"))
    )
    (net (code "48") (name "Net-(Q23-E)") (class "Default")
      (node (ref "Q23") (pin "2") (pinfunction "E_2") (pintype "passive"))
      (node (ref "R36") (pin "1") (pinfunction "1_1") (pintype "passive"))
      (node (ref "T7") (pin "3") (pinfunction "C_3") (pintype "passive"))
    )
    (net (code "49") (name "Net-(Q25-S)") (class "Default")
      (node (ref "Q25") (pin "2") (pinfunction "S_2") (pintype "passive"))
      (node (ref "Q28") (pin "3") (pinfunction "D_3") (pintype "passive"))
    )
    (net (code "50") (name "Net-(Q29-D)") (class "Default")
      (node (ref "Q29") (pin "3") (pinfunction "D_3") (pintype "passive"))
      (node (ref "R35") (pin "1") (pinfunction "1_1") (pintype "passive"))
      (node (ref "T7") (pin "1") (pinfunction "B_1") (pintype "passive"))
    )
    (net (code "51") (name "Net-(Q29-G)") (class "Default")
      (node (ref "Q29") (pin "1") (pinfunction "G_1") (pintype "passive"))
      (node (ref "Q30") (pin "3") (pinfunction "D_3") (pintype "passive"))
      (node (ref "R32") (pin "1") (pinfunction "1_1") (pintype "passive"))
      (node (ref "R34") (pin "1") (pinfunction "1_1") (pintype "passive"))
    )
    (net (code "52") (name "Net-(Q30-S)") (class "Default")
      (node (ref "Q30") (pin "2") (pinfunction "S_2") (pintype "passive"))
      (node (ref "Q31") (pin "3") (pinfunction "D_3") (pintype "passive"))
    )
    (net (code "53") (name "Net-(Q33-D)") (class "Default")
      (node (ref "Q33") (pin "3") (pinfunction "D_3") (pintype "passive"))
      (node (ref "R45") (pin "1") (pinfunction "1_1") (pintype "passive"))
    )
    (net (code "54") (name "Net-(T5-E)") (class "Default")
      (node (ref "T5") (pin "2") (pinfunction "E_2") (pintype "passive"))
      (node (ref "T6") (pin "2") (pinfunction "E_2") (pintype "passive"))
      (node (ref "T8") (pin "3") (pinfunction "C_3") (pintype "passive"))
    )
    (net (code "55") (name "Net-(T8-B)") (class "Default")
      (node (ref "D6") (pin "A") (pinfunction "A_A") (pintype "passive"))
      (node (ref "R37") (pin "2") (pinfunction "2_2") (pintype "passive"))
      (node (ref "T8") (pin "1") (pinfunction "B_1") (pintype "passive"))
    )
    (net (code "56") (name "Net-(T8-E)") (class "Default")
      (node (ref "R25") (pin "1") (pinfunction "1_1") (pintype "passive"))
      (node (ref "T8") (pin "2") (pinfunction "E_2") (pintype "passive"))
    )
  )
)
